# FPGA_Bank_2.net
KiCad netlist of a schematic drawn in Altium Designer
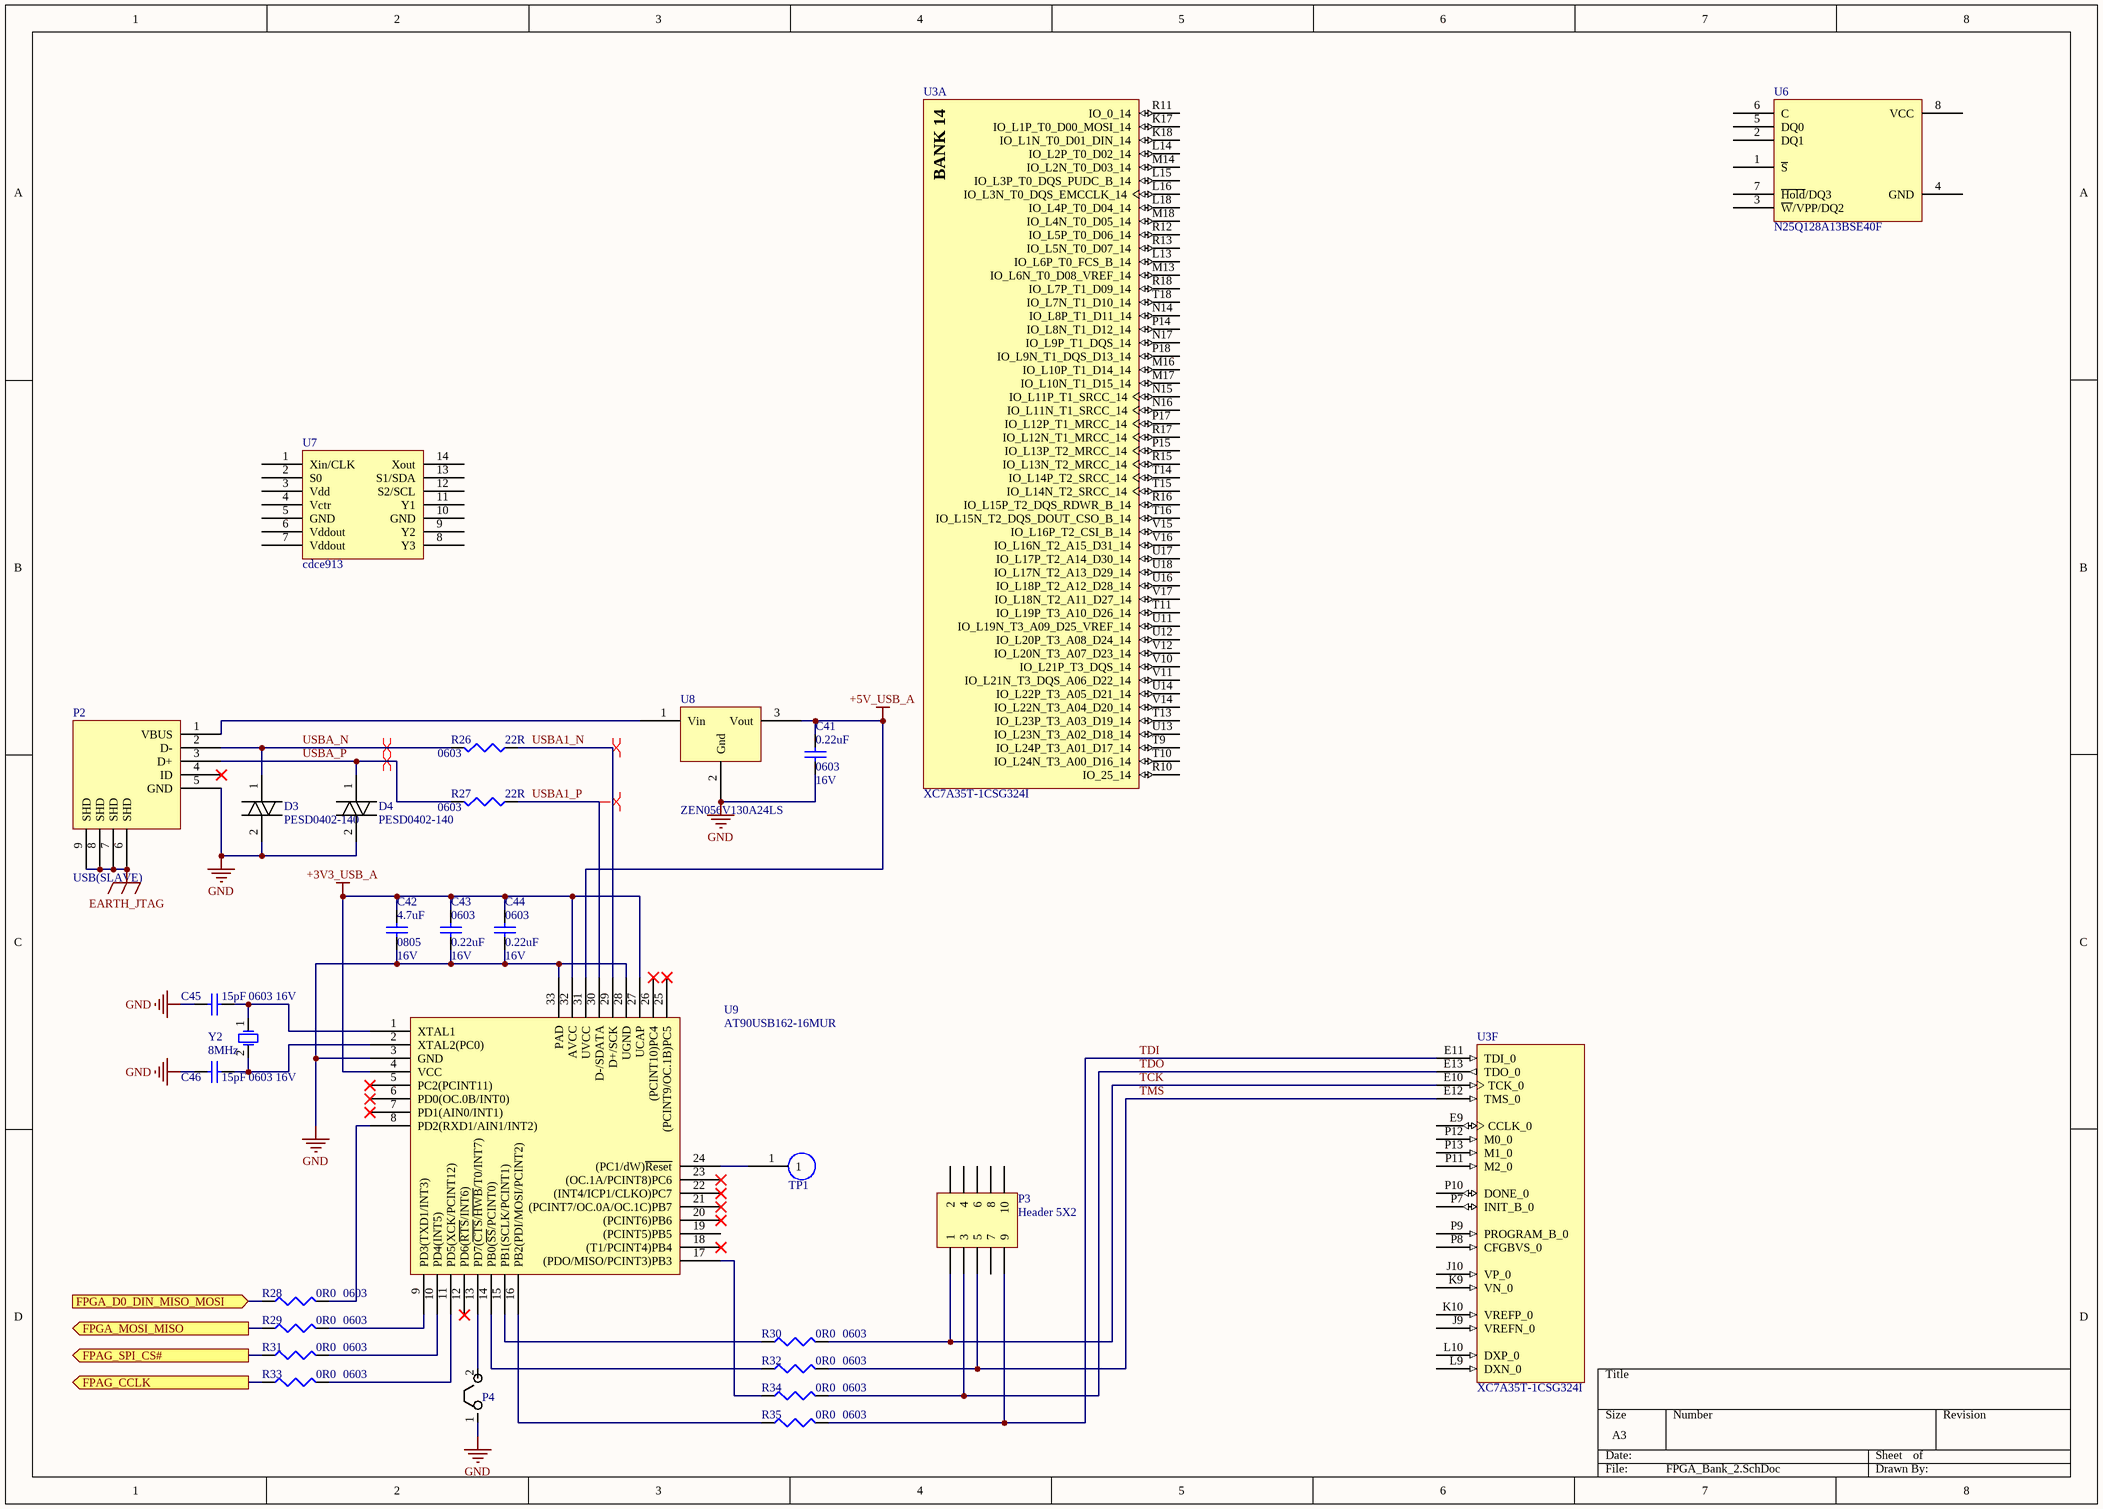
[diagram p0: FPGA_Bank_2.SchDoc]

(export (version "E")
  (design (tool "Eeschema 10.0.6"))
  (components
    (comp (ref "C41")
      (value "0.22uF")
      (footprint "1608[0603]")
      (description "Capacitor (Semiconductor SIM Model)")
      (fields
        (field (name "PACKAGEREFERENCE") "0603")
        (field (name "V") "16V")
        (field (name "PUBLISHER") "Altium Limited")
      )
      (libsource (lib "Devices") (part "Cap Semi"))
    )
    (comp (ref "C42")
      (value "4.7uF")
      (footprint "2012[0805]")
      (description "Capacitor (Semiconductor SIM Model)")
      (fields
        (field (name "PACKAGEREFERENCE") "0805")
        (field (name "V") "16V")
        (field (name "PUBLISHER") "Altium Limited")
      )
      (libsource (lib "Devices") (part "Cap Semi"))
    )
    (comp (ref "C43")
      (value "0.22uF")
      (footprint "1608[0603]")
      (description "Capacitor (Semiconductor SIM Model)")
      (fields
        (field (name "PACKAGEREFERENCE") "0603")
        (field (name "V") "16V")
        (field (name "PUBLISHER") "Altium Limited")
      )
      (libsource (lib "Devices") (part "Cap Semi"))
    )
    (comp (ref "C44")
      (value "0.22uF")
      (footprint "1608[0603]")
      (description "Capacitor (Semiconductor SIM Model)")
      (fields
        (field (name "PACKAGEREFERENCE") "0603")
        (field (name "V") "16V")
        (field (name "PUBLISHER") "Altium Limited")
      )
      (libsource (lib "Devices") (part "Cap Semi"))
    )
    (comp (ref "C45")
      (value "15pF")
      (footprint "1608[0603]")
      (description "Capacitor (Semiconductor SIM Model)")
      (fields
        (field (name "PACKAGEREFERENCE") "0603")
        (field (name "V") "16V")
        (field (name "PUBLISHER") "Altium Limited")
      )
      (libsource (lib "Devices") (part "Cap Semi"))
    )
    (comp (ref "C46")
      (value "15pF")
      (footprint "1608[0603]")
      (description "Capacitor (Semiconductor SIM Model)")
      (fields
        (field (name "PACKAGEREFERENCE") "0603")
        (field (name "V") "16V")
        (field (name "PUBLISHER") "Altium Limited")
      )
      (libsource (lib "Devices") (part "Cap Semi"))
    )
    (comp (ref "D3")
      (value "PESD0402-140")
      (footprint "PESD0402-140")
      (description "ESD保护器件")
      (libsource (lib "Spartan6_LX9_A0") (part "PESD0402-140"))
    )
    (comp (ref "D4")
      (value "PESD0402-140")
      (footprint "PESD0402-140")
      (description "ESD保护器件")
      (libsource (lib "Spartan6_LX9_A0") (part "PESD0402-140"))
    )
    (comp (ref "P2")
      (value "USB(SLAVE)")
      (footprint "USB_MINI_Btype")
      (description "USB座")
      (libsource (lib "Spartan6_LX9_A0") (part "USB(SLAVE)"))
    )
    (comp (ref "P3")
      (value "Header 5X2")
      (footprint "HDR2X5")
      (description "Header, 5-Pin, Dual row")
      (fields (field (name "PUBLISHER") "Altium Limited"))
      (libsource (lib "Miscellaneous Connectors") (part "Header 5X2"))
    )
    (comp (ref "P4") (value "DNP") (footprint "DNP") (libsource (lib "Spartan6_LX9_A0") (part "DNP")))
    (comp (ref "R26")
      (value "22R")
      (footprint "1608[0603]")
      (description "Resistor")
      (fields
        (field (name "PACKAGEREFERENCE") "0603")
        (field (name "Comment") "Res3")
        (field (name "PUBLISHER") "Altium Limited")
      )
      (libsource (lib "Miscellaneous Devices") (part "Res3"))
    )
    (comp (ref "R27")
      (value "22R")
      (footprint "1608[0603]")
      (description "Resistor")
      (fields
        (field (name "PACKAGEREFERENCE") "0603")
        (field (name "Comment") "Res3")
        (field (name "PUBLISHER") "Altium Limited")
      )
      (libsource (lib "Miscellaneous Devices") (part "Res3"))
    )
    (comp (ref "R28")
      (value "0R0")
      (footprint "1608[0603]")
      (description "Resistor")
      (fields
        (field (name "PACKAGEREFERENCE") "0603")
        (field (name "Comment") "Res3")
        (field (name "PUBLISHER") "Altium Limited")
      )
      (libsource (lib "Miscellaneous Devices") (part "Res3"))
    )
    (comp (ref "R29")
      (value "0R0")
      (footprint "1608[0603]")
      (description "Resistor")
      (fields
        (field (name "PACKAGEREFERENCE") "0603")
        (field (name "Comment") "Res3")
        (field (name "PUBLISHER") "Altium Limited")
      )
      (libsource (lib "Miscellaneous Devices") (part "Res3"))
    )
    (comp (ref "R30")
      (value "0R0")
      (footprint "1608[0603]")
      (description "Resistor")
      (fields
        (field (name "PACKAGEREFERENCE") "0603")
        (field (name "Comment") "Res3")
        (field (name "PUBLISHER") "Altium Limited")
      )
      (libsource (lib "Miscellaneous Devices") (part "Res3"))
    )
    (comp (ref "R31")
      (value "0R0")
      (footprint "1608[0603]")
      (description "Resistor")
      (fields
        (field (name "PACKAGEREFERENCE") "0603")
        (field (name "Comment") "Res3")
        (field (name "PUBLISHER") "Altium Limited")
      )
      (libsource (lib "Miscellaneous Devices") (part "Res3"))
    )
    (comp (ref "R32")
      (value "0R0")
      (footprint "1608[0603]")
      (description "Resistor")
      (fields
        (field (name "PACKAGEREFERENCE") "0603")
        (field (name "Comment") "Res3")
        (field (name "PUBLISHER") "Altium Limited")
      )
      (libsource (lib "Miscellaneous Devices") (part "Res3"))
    )
    (comp (ref "R33")
      (value "0R0")
      (footprint "1608[0603]")
      (description "Resistor")
      (fields
        (field (name "PACKAGEREFERENCE") "0603")
        (field (name "Comment") "Res3")
        (field (name "PUBLISHER") "Altium Limited")
      )
      (libsource (lib "Miscellaneous Devices") (part "Res3"))
    )
    (comp (ref "R34")
      (value "0R0")
      (footprint "1608[0603]")
      (description "Resistor")
      (fields
        (field (name "PACKAGEREFERENCE") "0603")
        (field (name "Comment") "Res3")
        (field (name "PUBLISHER") "Altium Limited")
      )
      (libsource (lib "Miscellaneous Devices") (part "Res3"))
    )
    (comp (ref "R35")
      (value "0R0")
      (footprint "1608[0603]")
      (description "Resistor")
      (fields
        (field (name "PACKAGEREFERENCE") "0603")
        (field (name "Comment") "Res3")
        (field (name "PUBLISHER") "Altium Limited")
      )
      (libsource (lib "Miscellaneous Devices") (part "Res3"))
    )
    (comp (ref "TP1") (value "TP") (libsource (lib "Spartan6_LX9_A0") (part "TP")))
    (comp (ref "U3")
      (value "XC7A35T-1CSG324I")
      (footprint "CSG324")
      (description "Artix-7 FPGA, 210 User I/Os, 0 GTP, 324-Ball BGA, Speed Grade 1, Industrial Grade, Pb-Free")
      (fields (field (name "MANUFACTURER") "Xilinx"))
      (libsource (lib "Xilinx Artix-7") (part "XC7A35T-1CSG324I"))
    )
    (comp (ref "U6")
      (value "N25Q128A13BSE40F")
      (footprint "N25Q128A13BSE40F[SOP-8]")
      (description "128Mb, 3V, Multiple I/O Serial Flash Memory")
      (fields (field (name "MANF") "Micron"))
      (libsource (lib "Spartan6_LX9_A0") (part "N25Q128A13BSE40F"))
    )
    (comp (ref "U7")
      (value "cdce913")
      (footprint "CDCE913[TSSOP-14]")
      (description "Flexible Low Power LVCMOS Clock Generator With SSC Support for EMI Reduction")
      (fields (field (name "MANF") "TI"))
      (libsource (lib "Spartan6_LX9_A0") (part "cdce913"))
    )
    (comp (ref "U8")
      (value "ZEN056V130A24LS")
      (footprint "ZEN056")
      (description "电压瞬态抑制器")
      (libsource (lib "Spartan6_LX9_A0") (part "ZEN056V130A24LS"))
    )
    (comp (ref "U9")
      (value "AT90USB162-16MUR")
      (footprint "AT90USB162-16MUR")
      (libsource (lib "Spartan6_LX9_A0") (part "AT90USB162-16MUR"))
    )
    (comp (ref "Y2")
      (value "8MHz")
      (footprint "XTAL_A")
      (description "Crystal Oscillator")
      (fields (field (name "PUBLISHER") "Altium Limited"))
      (libsource (lib "Devices") (part "XTAL"))
    )
  )
  (nets
    (net (code "1") (name "+3V3_USB_A") (class "Default")
      (node (ref "C42") (pin "1") (pinfunction "1_1") (pintype "passive"))
      (node (ref "C43") (pin "1") (pinfunction "1_1") (pintype "passive"))
      (node (ref "C44") (pin "1") (pinfunction "1_1") (pintype "passive"))
      (node (ref "U9") (pin "27") (pinfunction "UCAP_27") (pintype "passive"))
      (node (ref "U9") (pin "32") (pinfunction "AVCC_32") (pintype "passive"))
      (node (ref "U9") (pin "4") (pinfunction "VCC_4") (pintype "passive"))
    )
    (net (code "2") (name "+5V_USB_A") (class "Default")
      (node (ref "C41") (pin "1") (pinfunction "1_1") (pintype "passive"))
      (node (ref "U8") (pin "3") (pinfunction "Vout_3") (pintype "passive"))
      (node (ref "U9") (pin "31") (pinfunction "UVCC_31") (pintype "passive"))
    )
    (net (code "3") (name "/FPAG_CCLK") (class "Default")
      (node (ref "R33") (pin "1") (pinfunction "1_1") (pintype "passive"))
    )
    (net (code "4") (name "/FPAG_SPI_CS#") (class "Default")
      (node (ref "R31") (pin "1") (pinfunction "1_1") (pintype "passive"))
    )
    (net (code "5") (name "/FPGA_D0_DIN_MISO_MOSI") (class "Default")
      (node (ref "R28") (pin "1") (pinfunction "1_1") (pintype "passive"))
    )
    (net (code "6") (name "/FPGA_MOSI_MISO") (class "Default")
      (node (ref "R29") (pin "1") (pinfunction "1_1") (pintype "passive"))
    )
    (net (code "7") (name "/TCK") (class "Default")
      (node (ref "P3") (pin "1") (pinfunction "1_1") (pintype "passive"))
      (node (ref "R30") (pin "2") (pinfunction "2_2") (pintype "passive"))
      (node (ref "U3") (pin "E10") (pinfunction "TCK_0_E10") (pintype "input"))
    )
    (net (code "8") (name "/TDI") (class "Default")
      (node (ref "P3") (pin "9") (pinfunction "9_9") (pintype "passive"))
      (node (ref "R35") (pin "2") (pinfunction "2_2") (pintype "passive"))
      (node (ref "U3") (pin "E11") (pinfunction "TDI_0_E11") (pintype "input"))
    )
    (net (code "9") (name "/TDO") (class "Default")
      (node (ref "P3") (pin "3") (pinfunction "3_3") (pintype "passive"))
      (node (ref "R34") (pin "2") (pinfunction "2_2") (pintype "passive"))
      (node (ref "U3") (pin "E13") (pinfunction "TDO_0_E13") (pintype "output"))
    )
    (net (code "10") (name "/TMS") (class "Default")
      (node (ref "P3") (pin "5") (pinfunction "5_5") (pintype "passive"))
      (node (ref "R32") (pin "2") (pinfunction "2_2") (pintype "passive"))
      (node (ref "U3") (pin "E12") (pinfunction "TMS_0_E12") (pintype "input"))
    )
    (net (code "11") (name "/USBA1_N") (class "Default")
      (node (ref "R26") (pin "1") (pinfunction "1_1") (pintype "passive"))
      (node (ref "U9") (pin "29") (pinfunction "D+/SCK_29") (pintype "passive"))
    )
    (net (code "12") (name "/USBA1_P") (class "Default")
      (node (ref "R27") (pin "1") (pinfunction "1_1") (pintype "passive"))
      (node (ref "U9") (pin "30") (pinfunction "D-/SDATA_30") (pintype "passive"))
    )
    (net (code "13") (name "/USBA_N") (class "Default")
      (node (ref "D3") (pin "1") (pinfunction "1_1") (pintype "passive"))
      (node (ref "P2") (pin "2") (pinfunction "D-_2") (pintype "passive"))
      (node (ref "R26") (pin "2") (pinfunction "2_2") (pintype "passive"))
    )
    (net (code "14") (name "/USBA_P") (class "Default")
      (node (ref "D4") (pin "1") (pinfunction "1_1") (pintype "passive"))
      (node (ref "P2") (pin "3") (pinfunction "D+_3") (pintype "passive"))
      (node (ref "R27") (pin "2") (pinfunction "2_2") (pintype "passive"))
    )
    (net (code "15") (name "EARTH_JTAG") (class "Default")
      (node (ref "P2") (pin "6") (pinfunction "SHD_6") (pintype "passive"))
      (node (ref "P2") (pin "7") (pinfunction "SHD_7") (pintype "passive"))
      (node (ref "P2") (pin "8") (pinfunction "SHD_8") (pintype "passive"))
      (node (ref "P2") (pin "9") (pinfunction "SHD_9") (pintype "passive"))
    )
    (net (code "16") (name "GND") (class "Default")
      (node (ref "C41") (pin "2") (pinfunction "2_2") (pintype "passive"))
      (node (ref "C42") (pin "2") (pinfunction "2_2") (pintype "passive"))
      (node (ref "C43") (pin "2") (pinfunction "2_2") (pintype "passive"))
      (node (ref "C44") (pin "2") (pinfunction "2_2") (pintype "passive"))
      (node (ref "C45") (pin "2") (pinfunction "2_2") (pintype "passive"))
      (node (ref "C46") (pin "2") (pinfunction "2_2") (pintype "passive"))
      (node (ref "D3") (pin "2") (pinfunction "2_2") (pintype "passive"))
      (node (ref "D4") (pin "2") (pinfunction "2_2") (pintype "passive"))
      (node (ref "P2") (pin "5") (pinfunction "GND_5") (pintype "passive"))
      (node (ref "P4") (pin "1") (pinfunction "1_1") (pintype "passive"))
      (node (ref "U8") (pin "2") (pinfunction "Gnd_2") (pintype "passive"))
      (node (ref "U9") (pin "28") (pinfunction "UGND_28") (pintype "passive"))
      (node (ref "U9") (pin "3") (pinfunction "GND_3") (pintype "passive"))
      (node (ref "U9") (pin "33") (pinfunction "PAD_33") (pintype "passive"))
    )
    (net (code "17") (name "Net-(P2-VBUS)") (class "Default")
      (node (ref "P2") (pin "1") (pinfunction "VBUS_1") (pintype "passive"))
      (node (ref "U8") (pin "1") (pinfunction "Vin_1") (pintype "passive"))
    )
    (net (code "18") (name "Net-(U9-(PC1{slash}dW)~{Reset})") (class "Default")
      (node (ref "TP1") (pin "1") (pinfunction "1_1") (pintype "passive"))
      (node (ref "U9") (pin "24") (pinfunction "(PC1/dW)~{Reset}_24") (pintype "passive"))
    )
    (net (code "19") (name "Net-(U9-(PDO{slash}MISO{slash}PCINT3)PB3)") (class "Default")
      (node (ref "R34") (pin "1") (pinfunction "1_1") (pintype "passive"))
      (node (ref "U9") (pin "17") (pinfunction "(PDO/MISO/PCINT3)PB3_17") (pintype "passive"))
    )
    (net (code "20") (name "Net-(U9-PB0(~{SS}{slash}PCINT0))") (class "Default")
      (node (ref "R32") (pin "1") (pinfunction "1_1") (pintype "passive"))
      (node (ref "U9") (pin "14") (pinfunction "PB0(~{SS}/PCINT0)_14") (pintype "passive"))
    )
    (net (code "21") (name "Net-(U9-PB1(SCLK{slash}PCINT1))") (class "Default")
      (node (ref "R30") (pin "1") (pinfunction "1_1") (pintype "passive"))
      (node (ref "U9") (pin "15") (pinfunction "PB1(SCLK/PCINT1)_15") (pintype "passive"))
    )
    (net (code "22") (name "Net-(U9-PB2(PDI{slash}MOSI{slash}PCINT2))") (class "Default")
      (node (ref "R35") (pin "1") (pinfunction "1_1") (pintype "passive"))
      (node (ref "U9") (pin "16") (pinfunction "PB2(PDI/MOSI/PCINT2)_16") (pintype "passive"))
    )
    (net (code "23") (name "Net-(U9-PD2(RXD1{slash}AIN1{slash}INT2))") (class "Default")
      (node (ref "R28") (pin "2") (pinfunction "2_2") (pintype "passive"))
      (node (ref "U9") (pin "8") (pinfunction "PD2(RXD1/AIN1/INT2)_8") (pintype "passive"))
    )
    (net (code "24") (name "Net-(U9-PD3(TXD1{slash}INT3))") (class "Default")
      (node (ref "R29") (pin "2") (pinfunction "2_2") (pintype "passive"))
      (node (ref "U9") (pin "9") (pinfunction "PD3(TXD1/INT3)_9") (pintype "passive"))
    )
    (net (code "25") (name "Net-(U9-PD4(INT5))") (class "Default")
      (node (ref "R31") (pin "2") (pinfunction "2_2") (pintype "passive"))
      (node (ref "U9") (pin "10") (pinfunction "PD4(INT5)_10") (pintype "passive"))
    )
    (net (code "26") (name "Net-(U9-PD5(XCK{slash}PCINT12))") (class "Default")
      (node (ref "R33") (pin "2") (pinfunction "2_2") (pintype "passive"))
      (node (ref "U9") (pin "11") (pinfunction "PD5(XCK/PCINT12)_11") (pintype "passive"))
    )
    (net (code "27") (name "Net-(U9-PD7(~{CTS}{slash}~{HWB}{slash}T0{slash}INT7))") (class "Default")
      (node (ref "P4") (pin "2") (pinfunction "2_2") (pintype "passive"))
      (node (ref "U9") (pin "13") (pinfunction "PD7(~{CTS}/~{HWB}/T0/INT7)_13") (pintype "passive"))
    )
    (net (code "28") (name "Net-(U9-XTAL1)") (class "Default")
      (node (ref "C45") (pin "1") (pinfunction "1_1") (pintype "passive"))
      (node (ref "U9") (pin "1") (pinfunction "XTAL1_1") (pintype "passive"))
      (node (ref "Y2") (pin "1") (pinfunction "OSC1_1") (pintype "passive"))
    )
    (net (code "29") (name "Net-(U9-XTAL2(PC0))") (class "Default")
      (node (ref "C46") (pin "1") (pinfunction "1_1") (pintype "passive"))
      (node (ref "U9") (pin "2") (pinfunction "XTAL2(PC0)_2") (pintype "passive"))
      (node (ref "Y2") (pin "2") (pinfunction "OSC2_2") (pintype "passive"))
    )
    (net (code "30") (name "unconnected-(P2-ID-Pad4)") (class "Default")
      (node (ref "P2") (pin "4") (pinfunction "ID_4") (pintype "passive+no_connect"))
    )
    (net (code "31") (name "unconnected-(P3-Pad2)") (class "Default")
      (node (ref "P3") (pin "2") (pinfunction "2_2") (pintype "passive"))
    )
    (net (code "32") (name "unconnected-(P3-Pad4)") (class "Default")
      (node (ref "P3") (pin "4") (pinfunction "4_4") (pintype "passive"))
    )
    (net (code "33") (name "unconnected-(P3-Pad6)") (class "Default")
      (node (ref "P3") (pin "6") (pinfunction "6_6") (pintype "passive"))
    )
    (net (code "34") (name "unconnected-(P3-Pad7)") (class "Default")
      (node (ref "P3") (pin "7") (pinfunction "7_7") (pintype "passive"))
    )
    (net (code "35") (name "unconnected-(P3-Pad8)") (class "Default")
      (node (ref "P3") (pin "8") (pinfunction "8_8") (pintype "passive"))
    )
    (net (code "36") (name "unconnected-(P3-Pad10)") (class "Default")
      (node (ref "P3") (pin "10") (pinfunction "10_10") (pintype "passive"))
    )
    (net (code "37") (name "unconnected-(U3A-IO_0_14-PadR11)") (class "Default")
      (node (ref "U3") (pin "R11") (pinfunction "IO_0_14_R11") (pintype "bidirectional"))
    )
    (net (code "38") (name "unconnected-(U3A-IO_25_14-PadR10)") (class "Default")
      (node (ref "U3") (pin "R10") (pinfunction "IO_25_14_R10") (pintype "bidirectional"))
    )
    (net (code "39") (name "unconnected-(U3A-IO_L1N_T0_D01_DIN_14-PadK18)") (class "Default")
      (node (ref "U3") (pin "K18") (pinfunction "IO_L1N_T0_D01_DIN_14_K18") (pintype "bidirectional"))
    )
    (net (code "40") (name "unconnected-(U3A-IO_L1P_T0_D00_MOSI_14-PadK17)") (class "Default")
      (node (ref "U3") (pin "K17") (pinfunction "IO_L1P_T0_D00_MOSI_14_K17") (pintype "bidirectional"))
    )
    (net (code "41") (name "unconnected-(U3A-IO_L2N_T0_D03_14-PadM14)") (class "Default")
      (node (ref "U3") (pin "M14") (pinfunction "IO_L2N_T0_D03_14_M14") (pintype "bidirectional"))
    )
    (net (code "42") (name "unconnected-(U3A-IO_L2P_T0_D02_14-PadL14)") (class "Default")
      (node (ref "U3") (pin "L14") (pinfunction "IO_L2P_T0_D02_14_L14") (pintype "bidirectional"))
    )
    (net (code "43") (name "unconnected-(U3A-IO_L3N_T0_DQS_EMCCLK_14-PadL16)") (class "Default")
      (node (ref "U3") (pin "L16") (pinfunction "IO_L3N_T0_DQS_EMCCLK_14_L16") (pintype "bidirectional"))
    )
    (net (code "44") (name "unconnected-(U3A-IO_L3P_T0_DQS_PUDC_B_14-PadL15)") (class "Default")
      (node (ref "U3") (pin "L15") (pinfunction "IO_L3P_T0_DQS_PUDC_B_14_L15") (pintype "bidirectional"))
    )
    (net (code "45") (name "unconnected-(U3A-IO_L4N_T0_D05_14-PadM18)") (class "Default")
      (node (ref "U3") (pin "M18") (pinfunction "IO_L4N_T0_D05_14_M18") (pintype "bidirectional"))
    )
    (net (code "46") (name "unconnected-(U3A-IO_L4P_T0_D04_14-PadL18)") (class "Default")
      (node (ref "U3") (pin "L18") (pinfunction "IO_L4P_T0_D04_14_L18") (pintype "bidirectional"))
    )
    (net (code "47") (name "unconnected-(U3A-IO_L5N_T0_D07_14-PadR13)") (class "Default")
      (node (ref "U3") (pin "R13") (pinfunction "IO_L5N_T0_D07_14_R13") (pintype "bidirectional"))
    )
    (net (code "48") (name "unconnected-(U3A-IO_L5P_T0_D06_14-PadR12)") (class "Default")
      (node (ref "U3") (pin "R12") (pinfunction "IO_L5P_T0_D06_14_R12") (pintype "bidirectional"))
    )
    (net (code "49") (name "unconnected-(U3A-IO_L6N_T0_D08_VREF_14-PadM13)") (class "Default")
      (node (ref "U3") (pin "M13") (pinfunction "IO_L6N_T0_D08_VREF_14_M13") (pintype "bidirectional"))
    )
    (net (code "50") (name "unconnected-(U3A-IO_L6P_T0_FCS_B_14-PadL13)") (class "Default")
      (node (ref "U3") (pin "L13") (pinfunction "IO_L6P_T0_FCS_B_14_L13") (pintype "bidirectional"))
    )
    (net (code "51") (name "unconnected-(U3A-IO_L7N_T1_D10_14-PadT18)") (class "Default")
      (node (ref "U3") (pin "T18") (pinfunction "IO_L7N_T1_D10_14_T18") (pintype "bidirectional"))
    )
    (net (code "52") (name "unconnected-(U3A-IO_L7P_T1_D09_14-PadR18)") (class "Default")
      (node (ref "U3") (pin "R18") (pinfunction "IO_L7P_T1_D09_14_R18") (pintype "bidirectional"))
    )
    (net (code "53") (name "unconnected-(U3A-IO_L8N_T1_D12_14-PadP14)") (class "Default")
      (node (ref "U3") (pin "P14") (pinfunction "IO_L8N_T1_D12_14_P14") (pintype "bidirectional"))
    )
    (net (code "54") (name "unconnected-(U3A-IO_L8P_T1_D11_14-PadN14)") (class "Default")
      (node (ref "U3") (pin "N14") (pinfunction "IO_L8P_T1_D11_14_N14") (pintype "bidirectional"))
    )
    (net (code "55") (name "unconnected-(U3A-IO_L9N_T1_DQS_D13_14-PadP18)") (class "Default")
      (node (ref "U3") (pin "P18") (pinfunction "IO_L9N_T1_DQS_D13_14_P18") (pintype "bidirectional"))
    )
    (net (code "56") (name "unconnected-(U3A-IO_L9P_T1_DQS_14-PadN17)") (class "Default")
      (node (ref "U3") (pin "N17") (pinfunction "IO_L9P_T1_DQS_14_N17") (pintype "bidirectional"))
    )
    (net (code "57") (name "unconnected-(U3A-IO_L10N_T1_D15_14-PadM17)") (class "Default")
      (node (ref "U3") (pin "M17") (pinfunction "IO_L10N_T1_D15_14_M17") (pintype "bidirectional"))
    )
    (net (code "58") (name "unconnected-(U3A-IO_L10P_T1_D14_14-PadM16)") (class "Default")
      (node (ref "U3") (pin "M16") (pinfunction "IO_L10P_T1_D14_14_M16") (pintype "bidirectional"))
    )
    (net (code "59") (name "unconnected-(U3A-IO_L11N_T1_SRCC_14-PadN16)") (class "Default")
      (node (ref "U3") (pin "N16") (pinfunction "IO_L11N_T1_SRCC_14_N16") (pintype "bidirectional"))
    )
    (net (code "60") (name "unconnected-(U3A-IO_L11P_T1_SRCC_14-PadN15)") (class "Default")
      (node (ref "U3") (pin "N15") (pinfunction "IO_L11P_T1_SRCC_14_N15") (pintype "bidirectional"))
    )
    (net (code "61") (name "unconnected-(U3A-IO_L12N_T1_MRCC_14-PadR17)") (class "Default")
      (node (ref "U3") (pin "R17") (pinfunction "IO_L12N_T1_MRCC_14_R17") (pintype "bidirectional"))
    )
    (net (code "62") (name "unconnected-(U3A-IO_L12P_T1_MRCC_14-PadP17)") (class "Default")
      (node (ref "U3") (pin "P17") (pinfunction "IO_L12P_T1_MRCC_14_P17") (pintype "bidirectional"))
    )
    (net (code "63") (name "unconnected-(U3A-IO_L13N_T2_MRCC_14-PadR15)") (class "Default")
      (node (ref "U3") (pin "R15") (pinfunction "IO_L13N_T2_MRCC_14_R15") (pintype "bidirectional"))
    )
    (net (code "64") (name "unconnected-(U3A-IO_L13P_T2_MRCC_14-PadP15)") (class "Default")
      (node (ref "U3") (pin "P15") (pinfunction "IO_L13P_T2_MRCC_14_P15") (pintype "bidirectional"))
    )
    (net (code "65") (name "unconnected-(U3A-IO_L14N_T2_SRCC_14-PadT15)") (class "Default")
      (node (ref "U3") (pin "T15") (pinfunction "IO_L14N_T2_SRCC_14_T15") (pintype "bidirectional"))
    )
    (net (code "66") (name "unconnected-(U3A-IO_L14P_T2_SRCC_14-PadT14)") (class "Default")
      (node (ref "U3") (pin "T14") (pinfunction "IO_L14P_T2_SRCC_14_T14") (pintype "bidirectional"))
    )
    (net (code "67") (name "unconnected-(U3A-IO_L15N_T2_DQS_DOUT_CSO_B_14-PadT16)") (class "Default")
      (node (ref "U3") (pin "T16") (pinfunction "IO_L15N_T2_DQS_DOUT_CSO_B_14_T16") (pintype "bidirectional"))
    )
    (net (code "68") (name "unconnected-(U3A-IO_L15P_T2_DQS_RDWR_B_14-PadR16)") (class "Default")
      (node (ref "U3") (pin "R16") (pinfunction "IO_L15P_T2_DQS_RDWR_B_14_R16") (pintype "bidirectional"))
    )
    (net (code "69") (name "unconnected-(U3A-IO_L16N_T2_A15_D31_14-PadV16)") (class "Default")
      (node (ref "U3") (pin "V16") (pinfunction "IO_L16N_T2_A15_D31_14_V16") (pintype "bidirectional"))
    )
    (net (code "70") (name "unconnected-(U3A-IO_L16P_T2_CSI_B_14-PadV15)") (class "Default")
      (node (ref "U3") (pin "V15") (pinfunction "IO_L16P_T2_CSI_B_14_V15") (pintype "bidirectional"))
    )
    (net (code "71") (name "unconnected-(U3A-IO_L17N_T2_A13_D29_14-PadU18)") (class "Default")
      (node (ref "U3") (pin "U18") (pinfunction "IO_L17N_T2_A13_D29_14_U18") (pintype "bidirectional"))
    )
    (net (code "72") (name "unconnected-(U3A-IO_L17P_T2_A14_D30_14-PadU17)") (class "Default")
      (node (ref "U3") (pin "U17") (pinfunction "IO_L17P_T2_A14_D30_14_U17") (pintype "bidirectional"))
    )
    (net (code "73") (name "unconnected-(U3A-IO_L18N_T2_A11_D27_14-PadV17)") (class "Default")
      (node (ref "U3") (pin "V17") (pinfunction "IO_L18N_T2_A11_D27_14_V17") (pintype "bidirectional"))
    )
    (net (code "74") (name "unconnected-(U3A-IO_L18P_T2_A12_D28_14-PadU16)") (class "Default")
      (node (ref "U3") (pin "U16") (pinfunction "IO_L18P_T2_A12_D28_14_U16") (pintype "bidirectional"))
    )
    (net (code "75") (name "unconnected-(U3A-IO_L19N_T3_A09_D25_VREF_14-PadU11)") (class "Default")
      (node (ref "U3") (pin "U11") (pinfunction "IO_L19N_T3_A09_D25_VREF_14_U11") (pintype "bidirectional"))
    )
    (net (code "76") (name "unconnected-(U3A-IO_L19P_T3_A10_D26_14-PadT11)") (class "Default")
      (node (ref "U3") (pin "T11") (pinfunction "IO_L19P_T3_A10_D26_14_T11") (pintype "bidirectional"))
    )
    (net (code "77") (name "unconnected-(U3A-IO_L20N_T3_A07_D23_14-PadV12)") (class "Default")
      (node (ref "U3") (pin "V12") (pinfunction "IO_L20N_T3_A07_D23_14_V12") (pintype "bidirectional"))
    )
    (net (code "78") (name "unconnected-(U3A-IO_L20P_T3_A08_D24_14-PadU12)") (class "Default")
      (node (ref "U3") (pin "U12") (pinfunction "IO_L20P_T3_A08_D24_14_U12") (pintype "bidirectional"))
    )
    (net (code "79") (name "unconnected-(U3A-IO_L21N_T3_DQS_A06_D22_14-PadV11)") (class "Default")
      (node (ref "U3") (pin "V11") (pinfunction "IO_L21N_T3_DQS_A06_D22_14_V11") (pintype "bidirectional"))
    )
    (net (code "80") (name "unconnected-(U3A-IO_L21P_T3_DQS_14-PadV10)") (class "Default")
      (node (ref "U3") (pin "V10") (pinfunction "IO_L21P_T3_DQS_14_V10") (pintype "bidirectional"))
    )
    (net (code "81") (name "unconnected-(U3A-IO_L22N_T3_A04_D20_14-PadV14)") (class "Default")
      (node (ref "U3") (pin "V14") (pinfunction "IO_L22N_T3_A04_D20_14_V14") (pintype "bidirectional"))
    )
    (net (code "82") (name "unconnected-(U3A-IO_L22P_T3_A05_D21_14-PadU14)") (class "Default")
      (node (ref "U3") (pin "U14") (pinfunction "IO_L22P_T3_A05_D21_14_U14") (pintype "bidirectional"))
    )
    (net (code "83") (name "unconnected-(U3A-IO_L23N_T3_A02_D18_14-PadU13)") (class "Default")
      (node (ref "U3") (pin "U13") (pinfunction "IO_L23N_T3_A02_D18_14_U13") (pintype "bidirectional"))
    )
    (net (code "84") (name "unconnected-(U3A-IO_L23P_T3_A03_D19_14-PadT13)") (class "Default")
      (node (ref "U3") (pin "T13") (pinfunction "IO_L23P_T3_A03_D19_14_T13") (pintype "bidirectional"))
    )
    (net (code "85") (name "unconnected-(U3A-IO_L24N_T3_A00_D16_14-PadT10)") (class "Default")
      (node (ref "U3") (pin "T10") (pinfunction "IO_L24N_T3_A00_D16_14_T10") (pintype "bidirectional"))
    )
    (net (code "86") (name "unconnected-(U3A-IO_L24P_T3_A01_D17_14-PadT9)") (class "Default")
      (node (ref "U3") (pin "T9") (pinfunction "IO_L24P_T3_A01_D17_14_T9") (pintype "bidirectional"))
    )
    (net (code "87") (name "unconnected-(U3F-CCLK_0-PadE9)") (class "Default")
      (node (ref "U3") (pin "E9") (pinfunction "CCLK_0_E9") (pintype "bidirectional"))
    )
    (net (code "88") (name "unconnected-(U3F-CFGBVS_0-PadP8)") (class "Default")
      (node (ref "U3") (pin "P8") (pinfunction "CFGBVS_0_P8") (pintype "input"))
    )
    (net (code "89") (name "unconnected-(U3F-DONE_0-PadP10)") (class "Default")
      (node (ref "U3") (pin "P10") (pinfunction "DONE_0_P10") (pintype "bidirectional"))
    )
    (net (code "90") (name "unconnected-(U3F-DXN_0-PadL9)") (class "Default")
      (node (ref "U3") (pin "L9") (pinfunction "DXN_0_L9") (pintype "input"))
    )
    (net (code "91") (name "unconnected-(U3F-DXP_0-PadL10)") (class "Default")
      (node (ref "U3") (pin "L10") (pinfunction "DXP_0_L10") (pintype "input"))
    )
    (net (code "92") (name "unconnected-(U3F-INIT_B_0-PadP7)") (class "Default")
      (node (ref "U3") (pin "P7") (pinfunction "INIT_B_0_P7") (pintype "bidirectional"))
    )
    (net (code "93") (name "unconnected-(U3F-M0_0-PadP12)") (class "Default")
      (node (ref "U3") (pin "P12") (pinfunction "M0_0_P12") (pintype "input"))
    )
    (net (code "94") (name "unconnected-(U3F-M1_0-PadP13)") (class "Default")
      (node (ref "U3") (pin "P13") (pinfunction "M1_0_P13") (pintype "input"))
    )
    (net (code "95") (name "unconnected-(U3F-M2_0-PadP11)") (class "Default")
      (node (ref "U3") (pin "P11") (pinfunction "M2_0_P11") (pintype "input"))
    )
    (net (code "96") (name "unconnected-(U3F-PROGRAM_B_0-PadP9)") (class "Default")
      (node (ref "U3") (pin "P9") (pinfunction "PROGRAM_B_0_P9") (pintype "input"))
    )
    (net (code "97") (name "unconnected-(U3F-VN_0-PadK9)") (class "Default")
      (node (ref "U3") (pin "K9") (pinfunction "VN_0_K9") (pintype "input"))
    )
    (net (code "98") (name "unconnected-(U3F-VP_0-PadJ10)") (class "Default")
      (node (ref "U3") (pin "J10") (pinfunction "VP_0_J10") (pintype "input"))
    )
    (net (code "99") (name "unconnected-(U3F-VREFN_0-PadJ9)") (class "Default")
      (node (ref "U3") (pin "J9") (pinfunction "VREFN_0_J9") (pintype "input"))
    )
    (net (code "100") (name "unconnected-(U3F-VREFP_0-PadK10)") (class "Default")
      (node (ref "U3") (pin "K10") (pinfunction "VREFP_0_K10") (pintype "input"))
    )
    (net (code "101") (name "unconnected-(U6-C-Pad6)") (class "Default")
      (node (ref "U6") (pin "6") (pinfunction "C_6") (pintype "passive"))
    )
    (net (code "102") (name "unconnected-(U6-DQ0-Pad5)") (class "Default")
      (node (ref "U6") (pin "5") (pinfunction "DQ0_5") (pintype "passive"))
    )
    (net (code "103") (name "unconnected-(U6-DQ1-Pad2)") (class "Default")
      (node (ref "U6") (pin "2") (pinfunction "DQ1_2") (pintype "passive"))
    )
    (net (code "104") (name "unconnected-(U6-GND-Pad4)") (class "Default")
      (node (ref "U6") (pin "4") (pinfunction "GND_4") (pintype "passive"))
    )
    (net (code "105") (name "unconnected-(U6-VCC-Pad8)") (class "Default")
      (node (ref "U6") (pin "8") (pinfunction "VCC_8") (pintype "passive"))
    )
    (net (code "106") (name "unconnected-(U6-~{Hold}{slash}DQ3-Pad7)") (class "Default")
      (node (ref "U6") (pin "7") (pinfunction "~{Hold}/DQ3_7") (pintype "passive"))
    )
    (net (code "107") (name "unconnected-(U6-~{S}-Pad1)") (class "Default")
      (node (ref "U6") (pin "1") (pinfunction "~{S}_1") (pintype "passive"))
    )
    (net (code "108") (name "unconnected-(U6-~{W}{slash}VPP{slash}DQ2-Pad3)") (class "Default")
      (node (ref "U6") (pin "3") (pinfunction "~{W}/VPP/DQ2_3") (pintype "passive"))
    )
    (net (code "109") (name "unconnected-(U7-GND-Pad5)") (class "Default")
      (node (ref "U7") (pin "5") (pinfunction "GND_5") (pintype "passive"))
    )
    (net (code "110") (name "unconnected-(U7-GND-Pad10)") (class "Default")
      (node (ref "U7") (pin "10") (pinfunction "GND_10") (pintype "passive"))
    )
    (net (code "111") (name "unconnected-(U7-S0-Pad2)") (class "Default")
      (node (ref "U7") (pin "2") (pinfunction "S0_2") (pintype "passive"))
    )
    (net (code "112") (name "unconnected-(U7-S1{slash}SDA-Pad13)") (class "Default")
      (node (ref "U7") (pin "13") (pinfunction "S1/SDA_13") (pintype "passive"))
    )
    (net (code "113") (name "unconnected-(U7-S2{slash}SCL-Pad12)") (class "Default")
      (node (ref "U7") (pin "12") (pinfunction "S2/SCL_12") (pintype "passive"))
    )
    (net (code "114") (name "unconnected-(U7-Vctr-Pad4)") (class "Default")
      (node (ref "U7") (pin "4") (pinfunction "Vctr_4") (pintype "passive"))
    )
    (net (code "115") (name "unconnected-(U7-Vdd-Pad3)") (class "Default")
      (node (ref "U7") (pin "3") (pinfunction "Vdd_3") (pintype "passive"))
    )
    (net (code "116") (name "unconnected-(U7-Vddout-Pad6)") (class "Default")
      (node (ref "U7") (pin "6") (pinfunction "Vddout_6") (pintype "passive"))
    )
    (net (code "117") (name "unconnected-(U7-Vddout-Pad7)") (class "Default")
      (node (ref "U7") (pin "7") (pinfunction "Vddout_7") (pintype "passive"))
    )
    (net (code "118") (name "unconnected-(U7-Xin{slash}CLK-Pad1)") (class "Default")
      (node (ref "U7") (pin "1") (pinfunction "Xin/CLK_1") (pintype "passive"))
    )
    (net (code "119") (name "unconnected-(U7-Xout-Pad14)") (class "Default")
      (node (ref "U7") (pin "14") (pinfunction "Xout_14") (pintype "passive"))
    )
    (net (code "120") (name "unconnected-(U7-Y1-Pad11)") (class "Default")
      (node (ref "U7") (pin "11") (pinfunction "Y1_11") (pintype "passive"))
    )
    (net (code "121") (name "unconnected-(U7-Y2-Pad9)") (class "Default")
      (node (ref "U7") (pin "9") (pinfunction "Y2_9") (pintype "passive"))
    )
    (net (code "122") (name "unconnected-(U7-Y3-Pad8)") (class "Default")
      (node (ref "U7") (pin "8") (pinfunction "Y3_8") (pintype "passive"))
    )
    (net (code "123") (name "unconnected-(U9-(INT4{slash}ICP1{slash}CLKO)PC7-Pad22)") (class "Default")
      (node (ref "U9") (pin "22") (pinfunction "(INT4/ICP1/CLKO)PC7_22") (pintype "passive+no_connect"))
    )
    (net (code "124") (name "unconnected-(U9-(OC.1A{slash}PCINT8)PC6-Pad23)") (class "Default")
      (node (ref "U9") (pin "23") (pinfunction "(OC.1A/PCINT8)PC6_23") (pintype "passive+no_connect"))
    )
    (net (code "125") (name "unconnected-(U9-(PCINT5)PB5-Pad19)") (class "Default")
      (node (ref "U9") (pin "19") (pinfunction "(PCINT5)PB5_19") (pintype "passive"))
    )
    (net (code "126") (name "unconnected-(U9-(PCINT6)PB6-Pad20)") (class "Default")
      (node (ref "U9") (pin "20") (pinfunction "(PCINT6)PB6_20") (pintype "passive+no_connect"))
    )
    (net (code "127") (name "unconnected-(U9-(PCINT7{slash}OC.0A{slash}OC.1C)PB7-Pad21)") (class "Default")
      (node (ref "U9") (pin "21") (pinfunction "(PCINT7/OC.0A/OC.1C)PB7_21") (pintype "passive+no_connect"))
    )
    (net (code "128") (name "unconnected-(U9-(PCINT9{slash}OC.1B)PC5-Pad25)") (class "Default")
      (node (ref "U9") (pin "25") (pinfunction "(PCINT9/OC.1B)PC5_25") (pintype "passive+no_connect"))
    )
    (net (code "129") (name "unconnected-(U9-(PCINT10)PC4-Pad26)") (class "Default")
      (node (ref "U9") (pin "26") (pinfunction "(PCINT10)PC4_26") (pintype "passive+no_connect"))
    )
    (net (code "130") (name "unconnected-(U9-(T1{slash}PCINT4)PB4-Pad18)") (class "Default")
      (node (ref "U9") (pin "18") (pinfunction "(T1/PCINT4)PB4_18") (pintype "passive+no_connect"))
    )
    (net (code "131") (name "unconnected-(U9-PC2(PCINT11)-Pad5)") (class "Default")
      (node (ref "U9") (pin "5") (pinfunction "PC2(PCINT11)_5") (pintype "passive+no_connect"))
    )
    (net (code "132") (name "unconnected-(U9-PD0(OC.0B{slash}INT0)-Pad6)") (class "Default")
      (node (ref "U9") (pin "6") (pinfunction "PD0(OC.0B/INT0)_6") (pintype "passive+no_connect"))
    )
    (net (code "133") (name "unconnected-(U9-PD1(AIN0{slash}INT1)-Pad7)") (class "Default")
      (node (ref "U9") (pin "7") (pinfunction "PD1(AIN0/INT1)_7") (pintype "passive+no_connect"))
    )
    (net (code "134") (name "unconnected-(U9-PD6(~{RTS}{slash}INT6)-Pad12)") (class "Default")
      (node (ref "U9") (pin "12") (pinfunction "PD6(~{RTS}/INT6)_12") (pintype "passive+no_connect"))
    )
  )
)
